# Cpcis_connectors_P4_P5_P6.net
KiCad netlist of a schematic drawn in Altium Designer
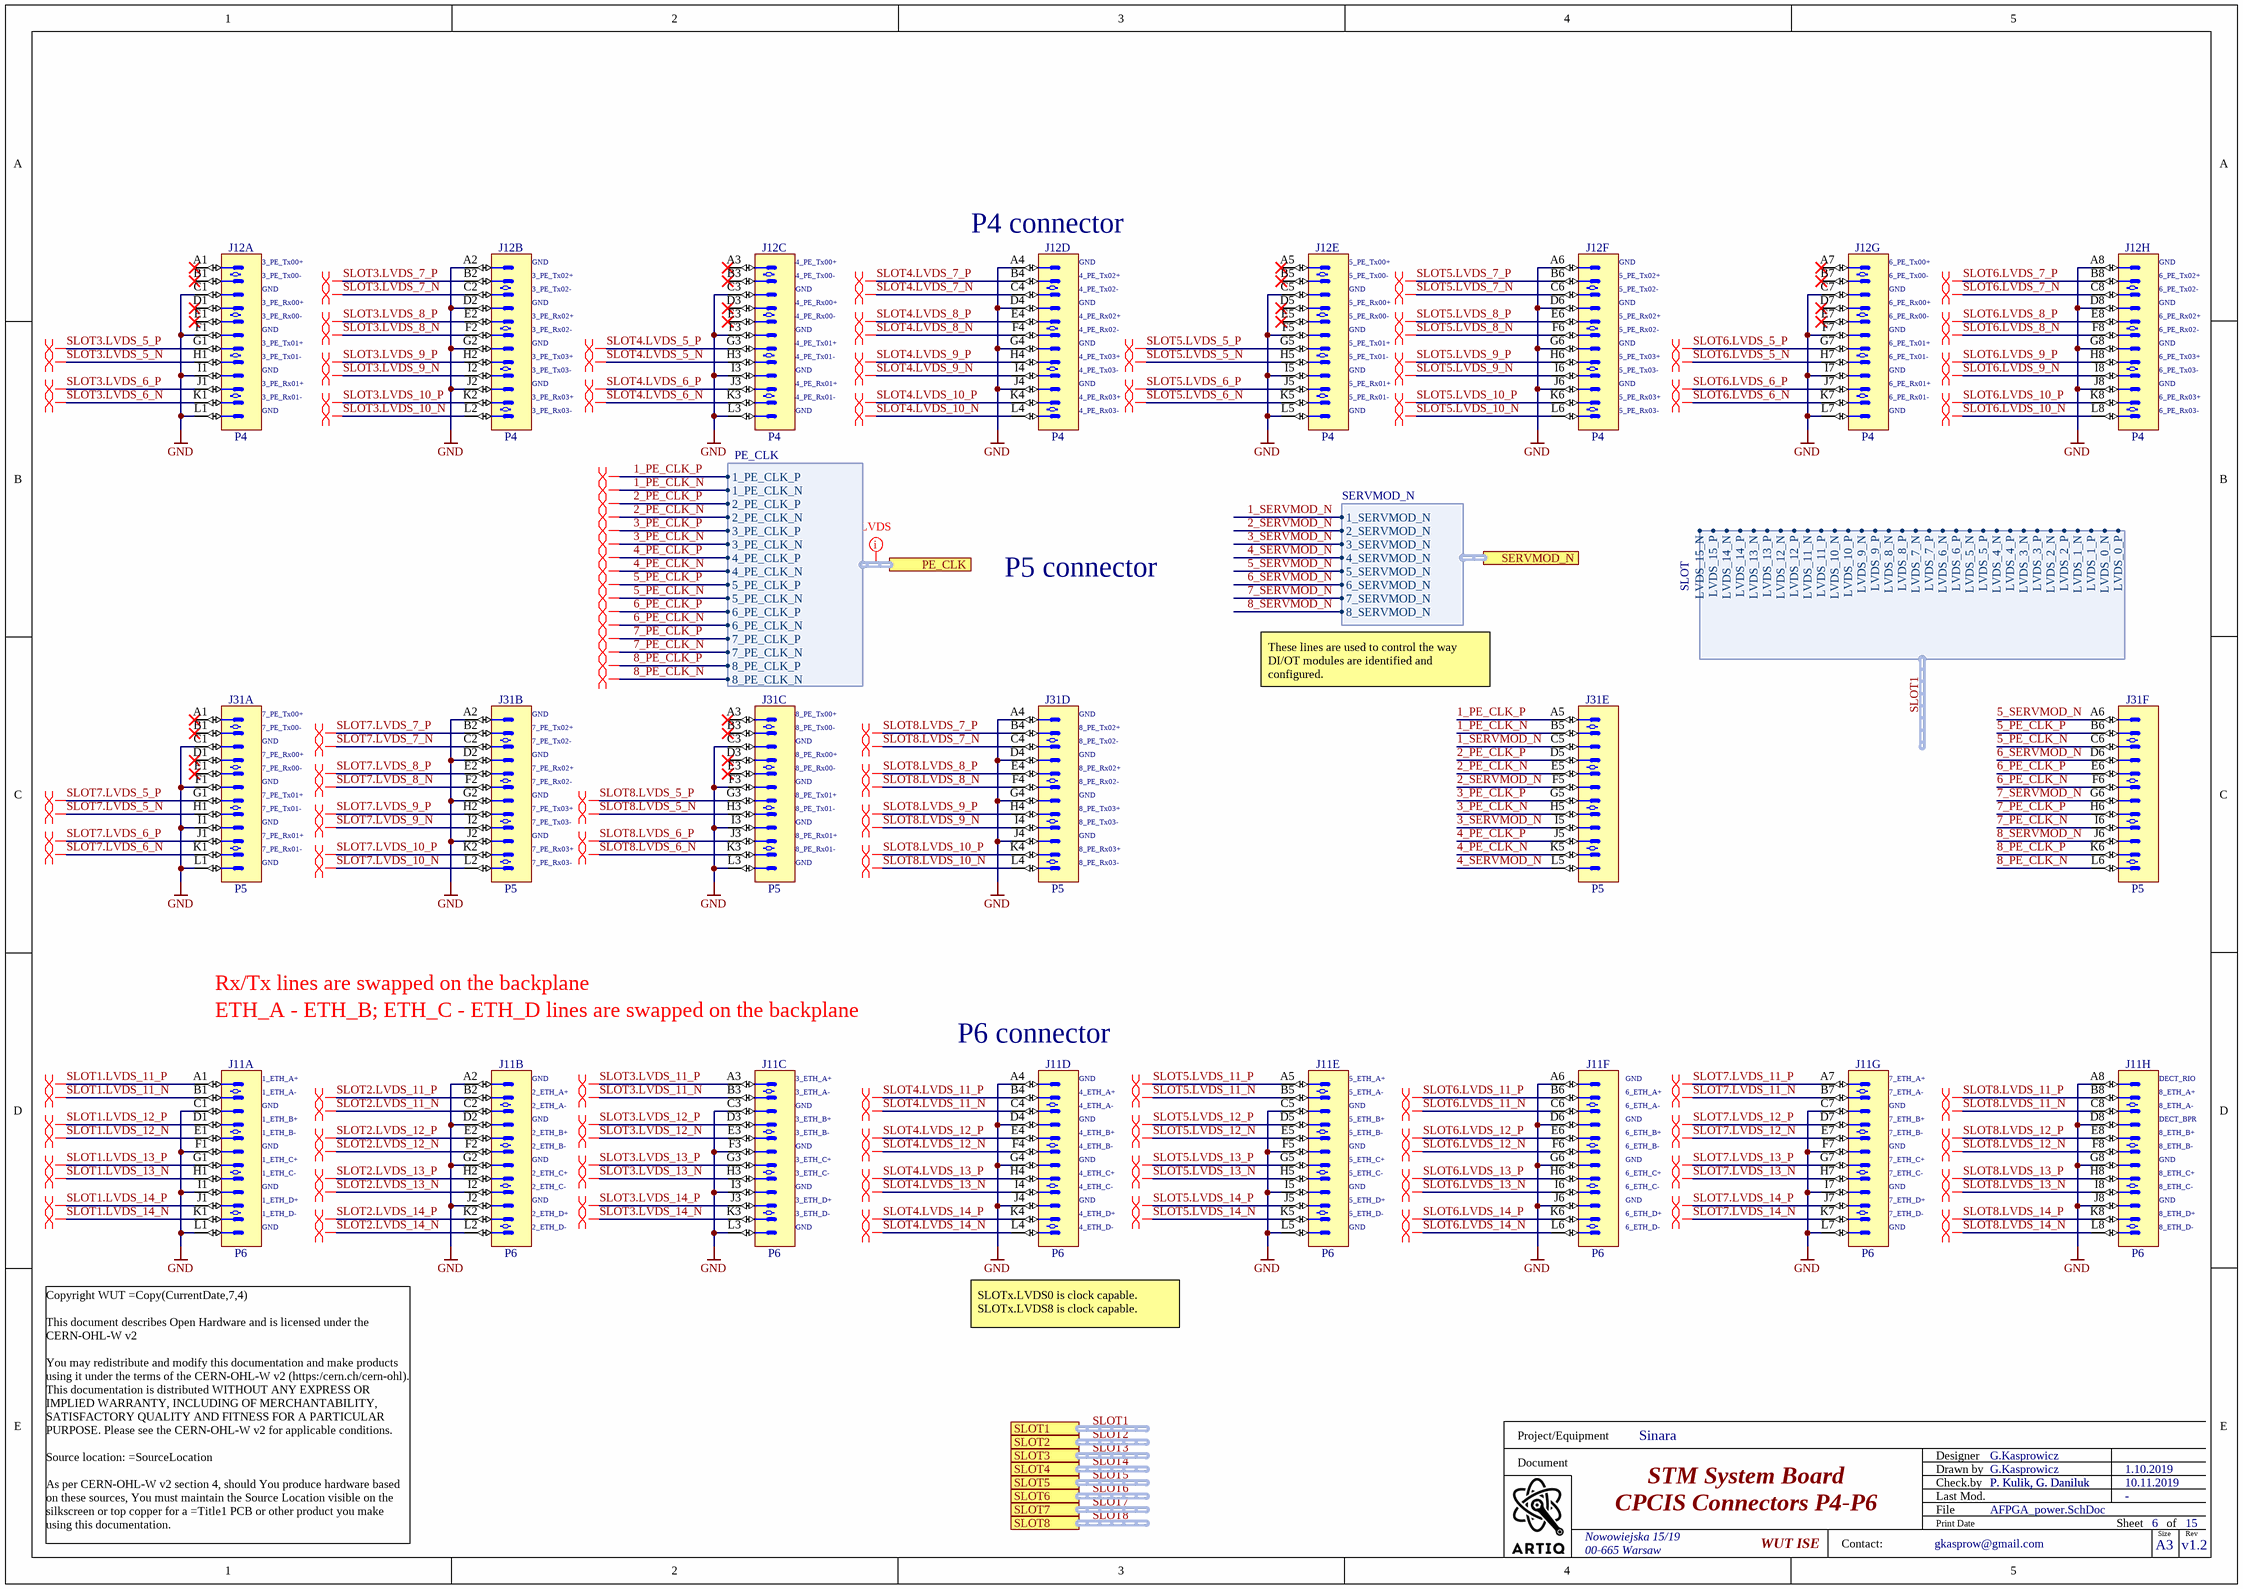
[diagram p0: Cpcis_connectors_P4_P5_P6.SchDoc]

(export (version "E")
  (design (tool "Eeschema 10.0.6"))
  (components
    (comp (ref "J11")
      (value "P6")
      (footprint "AMPHENOL_10052838-101LF")
      (description "96 Contacts Header, 8 Columns, 4 Pairs per Column")
      (fields
        (field (name "PART NUMBER") "AMPHENOL_10052838-101LF")
        (field (name "MANUFACTURER") "AMPHENOL")
        (field (name "AUTHOR") "CERN DEM MR")
      )
      (libsource (lib "Connectors") (part "AMPHENOL_10052838-101LF"))
    )
    (comp (ref "J12")
      (value "P4")
      (footprint "AMPHENOL_10052837-101LF")
      (description "96 Contacts Header, 8 Columns, 4 Pairs per Column")
      (fields
        (field (name "PART NUMBER") "AMPHENOL_10052837-101LF")
        (field (name "MANUFACTURER") "AMPHENOL")
        (field (name "AUTHOR") "CERN DEM MR")
      )
      (libsource (lib "Connectors") (part "AMPHENOL_10052837-101LF"))
    )
    (comp (ref "J31")
      (value "P5")
      (footprint "AMPHENOL_10052824-101LF")
      (description "72 Contacts Header, 6 Columns, 4 Pairs per Column")
      (fields
        (field (name "PART NUMBER") "AMPHENOL_10052824-101LF")
        (field (name "MANUFACTURER") "AMPHENOL")
        (field (name "AUTHOR") "CERN DEM JMW")
      )
      (libsource (lib "Connectors") (part "AMPHENOL_10052824-101LF"))
    )
  )
  (nets
    (net (code "11") (name "/1_PE_CLK_N") (class "Default")
      (node (ref "J31") (pin "B5") (pinfunction "B5_B5") (pintype "bidirectional"))
    )
    (net (code "12") (name "/1_PE_CLK_P") (class "Default")
      (node (ref "J31") (pin "A5") (pinfunction "A5_A5") (pintype "bidirectional"))
    )
    (net (code "13") (name "/1_SERVMOD_N") (class "Default")
      (node (ref "J31") (pin "C5") (pinfunction "C5_C5") (pintype "bidirectional"))
    )
    (net (code "14") (name "/2_PE_CLK_N") (class "Default")
      (node (ref "J31") (pin "E5") (pinfunction "E5_E5") (pintype "bidirectional"))
    )
    (net (code "15") (name "/2_PE_CLK_P") (class "Default")
      (node (ref "J31") (pin "D5") (pinfunction "D5_D5") (pintype "bidirectional"))
    )
    (net (code "16") (name "/2_SERVMOD_N") (class "Default")
      (node (ref "J31") (pin "F5") (pinfunction "F5_F5") (pintype "bidirectional"))
    )
    (net (code "17") (name "/3_PE_CLK_N") (class "Default")
      (node (ref "J31") (pin "H5") (pinfunction "H5_H5") (pintype "bidirectional"))
    )
    (net (code "18") (name "/3_PE_CLK_P") (class "Default")
      (node (ref "J31") (pin "G5") (pinfunction "G5_G5") (pintype "bidirectional"))
    )
    (net (code "19") (name "/3_SERVMOD_N") (class "Default")
      (node (ref "J31") (pin "I5") (pinfunction "I5_I5") (pintype "bidirectional"))
    )
    (net (code "20") (name "/4_PE_CLK_N") (class "Default")
      (node (ref "J31") (pin "K5") (pinfunction "K5_K5") (pintype "bidirectional"))
    )
    (net (code "21") (name "/4_PE_CLK_P") (class "Default")
      (node (ref "J31") (pin "J5") (pinfunction "J5_J5") (pintype "bidirectional"))
    )
    (net (code "22") (name "/4_SERVMOD_N") (class "Default")
      (node (ref "J31") (pin "L5") (pinfunction "L5_L5") (pintype "bidirectional"))
    )
    (net (code "23") (name "/5_PE_CLK_N") (class "Default")
      (node (ref "J31") (pin "C6") (pinfunction "C6_C6") (pintype "bidirectional"))
    )
    (net (code "24") (name "/5_PE_CLK_P") (class "Default")
      (node (ref "J31") (pin "B6") (pinfunction "B6_B6") (pintype "bidirectional"))
    )
    (net (code "25") (name "/5_SERVMOD_N") (class "Default")
      (node (ref "J31") (pin "A6") (pinfunction "A6_A6") (pintype "bidirectional"))
    )
    (net (code "26") (name "/6_PE_CLK_N") (class "Default")
      (node (ref "J31") (pin "F6") (pinfunction "F6_F6") (pintype "bidirectional"))
    )
    (net (code "27") (name "/6_PE_CLK_P") (class "Default")
      (node (ref "J31") (pin "E6") (pinfunction "E6_E6") (pintype "bidirectional"))
    )
    (net (code "28") (name "/6_SERVMOD_N") (class "Default")
      (node (ref "J31") (pin "D6") (pinfunction "D6_D6") (pintype "bidirectional"))
    )
    (net (code "29") (name "/7_PE_CLK_N") (class "Default")
      (node (ref "J31") (pin "I6") (pinfunction "I6_I6") (pintype "bidirectional"))
    )
    (net (code "30") (name "/7_PE_CLK_P") (class "Default")
      (node (ref "J31") (pin "H6") (pinfunction "H6_H6") (pintype "bidirectional"))
    )
    (net (code "31") (name "/7_SERVMOD_N") (class "Default")
      (node (ref "J31") (pin "G6") (pinfunction "G6_G6") (pintype "bidirectional"))
    )
    (net (code "32") (name "/8_PE_CLK_N") (class "Default")
      (node (ref "J31") (pin "L6") (pinfunction "L6_L6") (pintype "bidirectional"))
    )
    (net (code "33") (name "/8_PE_CLK_P") (class "Default")
      (node (ref "J31") (pin "K6") (pinfunction "K6_K6") (pintype "bidirectional"))
    )
    (net (code "34") (name "/8_SERVMOD_N") (class "Default")
      (node (ref "J31") (pin "J6") (pinfunction "J6_J6") (pintype "bidirectional"))
    )
    (net (code "35") (name "/SLOT1.LVDS_11_N") (class "Default")
      (node (ref "J11") (pin "B1") (pinfunction "B1_B1") (pintype "bidirectional"))
    )
    (net (code "36") (name "/SLOT1.LVDS_11_P") (class "Default")
      (node (ref "J11") (pin "A1") (pinfunction "A1_A1") (pintype "bidirectional"))
    )
    (net (code "37") (name "/SLOT1.LVDS_12_N") (class "Default")
      (node (ref "J11") (pin "E1") (pinfunction "E1_E1") (pintype "bidirectional"))
    )
    (net (code "38") (name "/SLOT1.LVDS_12_P") (class "Default")
      (node (ref "J11") (pin "D1") (pinfunction "D1_D1") (pintype "bidirectional"))
    )
    (net (code "39") (name "/SLOT1.LVDS_13_N") (class "Default")
      (node (ref "J11") (pin "H1") (pinfunction "H1_H1") (pintype "bidirectional"))
    )
    (net (code "40") (name "/SLOT1.LVDS_13_P") (class "Default")
      (node (ref "J11") (pin "G1") (pinfunction "G1_G1") (pintype "bidirectional"))
    )
    (net (code "41") (name "/SLOT1.LVDS_14_N") (class "Default")
      (node (ref "J11") (pin "K1") (pinfunction "K1_K1") (pintype "bidirectional"))
    )
    (net (code "42") (name "/SLOT1.LVDS_14_P") (class "Default")
      (node (ref "J11") (pin "J1") (pinfunction "J1_J1") (pintype "bidirectional"))
    )
    (net (code "44") (name "/SLOT2.LVDS_11_N") (class "Default")
      (node (ref "J11") (pin "C2") (pinfunction "C2_C2") (pintype "bidirectional"))
    )
    (net (code "45") (name "/SLOT2.LVDS_11_P") (class "Default")
      (node (ref "J11") (pin "B2") (pinfunction "B2_B2") (pintype "bidirectional"))
    )
    (net (code "46") (name "/SLOT2.LVDS_12_N") (class "Default")
      (node (ref "J11") (pin "F2") (pinfunction "F2_F2") (pintype "bidirectional"))
    )
    (net (code "47") (name "/SLOT2.LVDS_12_P") (class "Default")
      (node (ref "J11") (pin "E2") (pinfunction "E2_E2") (pintype "bidirectional"))
    )
    (net (code "48") (name "/SLOT2.LVDS_13_N") (class "Default")
      (node (ref "J11") (pin "I2") (pinfunction "I2_I2") (pintype "bidirectional"))
    )
    (net (code "49") (name "/SLOT2.LVDS_13_P") (class "Default")
      (node (ref "J11") (pin "H2") (pinfunction "H2_H2") (pintype "bidirectional"))
    )
    (net (code "50") (name "/SLOT2.LVDS_14_N") (class "Default")
      (node (ref "J11") (pin "L2") (pinfunction "L2_L2") (pintype "bidirectional"))
    )
    (net (code "51") (name "/SLOT2.LVDS_14_P") (class "Default")
      (node (ref "J11") (pin "K2") (pinfunction "K2_K2") (pintype "bidirectional"))
    )
    (net (code "52") (name "/SLOT3.LVDS_5_N") (class "Default")
      (node (ref "J12") (pin "H1") (pinfunction "H1_H1") (pintype "bidirectional"))
    )
    (net (code "53") (name "/SLOT3.LVDS_5_P") (class "Default")
      (node (ref "J12") (pin "G1") (pinfunction "G1_G1") (pintype "bidirectional"))
    )
    (net (code "54") (name "/SLOT3.LVDS_6_N") (class "Default")
      (node (ref "J12") (pin "K1") (pinfunction "K1_K1") (pintype "bidirectional"))
    )
    (net (code "55") (name "/SLOT3.LVDS_6_P") (class "Default")
      (node (ref "J12") (pin "J1") (pinfunction "J1_J1") (pintype "bidirectional"))
    )
    (net (code "56") (name "/SLOT3.LVDS_7_N") (class "Default")
      (node (ref "J12") (pin "C2") (pinfunction "C2_C2") (pintype "bidirectional"))
    )
    (net (code "57") (name "/SLOT3.LVDS_7_P") (class "Default")
      (node (ref "J12") (pin "B2") (pinfunction "B2_B2") (pintype "bidirectional"))
    )
    (net (code "58") (name "/SLOT3.LVDS_8_N") (class "Default")
      (node (ref "J12") (pin "F2") (pinfunction "F2_F2") (pintype "bidirectional"))
    )
    (net (code "59") (name "/SLOT3.LVDS_8_P") (class "Default")
      (node (ref "J12") (pin "E2") (pinfunction "E2_E2") (pintype "bidirectional"))
    )
    (net (code "60") (name "/SLOT3.LVDS_9_N") (class "Default")
      (node (ref "J12") (pin "I2") (pinfunction "I2_I2") (pintype "bidirectional"))
    )
    (net (code "61") (name "/SLOT3.LVDS_9_P") (class "Default")
      (node (ref "J12") (pin "H2") (pinfunction "H2_H2") (pintype "bidirectional"))
    )
    (net (code "62") (name "/SLOT3.LVDS_10_N") (class "Default")
      (node (ref "J12") (pin "L2") (pinfunction "L2_L2") (pintype "bidirectional"))
    )
    (net (code "63") (name "/SLOT3.LVDS_10_P") (class "Default")
      (node (ref "J12") (pin "K2") (pinfunction "K2_K2") (pintype "bidirectional"))
    )
    (net (code "64") (name "/SLOT3.LVDS_11_N") (class "Default")
      (node (ref "J11") (pin "B3") (pinfunction "B3_B3") (pintype "bidirectional"))
    )
    (net (code "65") (name "/SLOT3.LVDS_11_P") (class "Default")
      (node (ref "J11") (pin "A3") (pinfunction "A3_A3") (pintype "bidirectional"))
    )
    (net (code "66") (name "/SLOT3.LVDS_12_N") (class "Default")
      (node (ref "J11") (pin "E3") (pinfunction "E3_E3") (pintype "bidirectional"))
    )
    (net (code "67") (name "/SLOT3.LVDS_12_P") (class "Default")
      (node (ref "J11") (pin "D3") (pinfunction "D3_D3") (pintype "bidirectional"))
    )
    (net (code "68") (name "/SLOT3.LVDS_13_N") (class "Default")
      (node (ref "J11") (pin "H3") (pinfunction "H3_H3") (pintype "bidirectional"))
    )
    (net (code "69") (name "/SLOT3.LVDS_13_P") (class "Default")
      (node (ref "J11") (pin "G3") (pinfunction "G3_G3") (pintype "bidirectional"))
    )
    (net (code "70") (name "/SLOT3.LVDS_14_N") (class "Default")
      (node (ref "J11") (pin "K3") (pinfunction "K3_K3") (pintype "bidirectional"))
    )
    (net (code "71") (name "/SLOT3.LVDS_14_P") (class "Default")
      (node (ref "J11") (pin "J3") (pinfunction "J3_J3") (pintype "bidirectional"))
    )
    (net (code "72") (name "/SLOT4.LVDS_5_N") (class "Default")
      (node (ref "J12") (pin "H3") (pinfunction "H3_H3") (pintype "bidirectional"))
    )
    (net (code "73") (name "/SLOT4.LVDS_5_P") (class "Default")
      (node (ref "J12") (pin "G3") (pinfunction "G3_G3") (pintype "bidirectional"))
    )
    (net (code "74") (name "/SLOT4.LVDS_6_N") (class "Default")
      (node (ref "J12") (pin "K3") (pinfunction "K3_K3") (pintype "bidirectional"))
    )
    (net (code "75") (name "/SLOT4.LVDS_6_P") (class "Default")
      (node (ref "J12") (pin "J3") (pinfunction "J3_J3") (pintype "bidirectional"))
    )
    (net (code "76") (name "/SLOT4.LVDS_7_N") (class "Default")
      (node (ref "J12") (pin "C4") (pinfunction "C4_C4") (pintype "bidirectional"))
    )
    (net (code "77") (name "/SLOT4.LVDS_7_P") (class "Default")
      (node (ref "J12") (pin "B4") (pinfunction "B4_B4") (pintype "bidirectional"))
    )
    (net (code "78") (name "/SLOT4.LVDS_8_N") (class "Default")
      (node (ref "J12") (pin "F4") (pinfunction "F4_F4") (pintype "bidirectional"))
    )
    (net (code "79") (name "/SLOT4.LVDS_8_P") (class "Default")
      (node (ref "J12") (pin "E4") (pinfunction "E4_E4") (pintype "bidirectional"))
    )
    (net (code "80") (name "/SLOT4.LVDS_9_N") (class "Default")
      (node (ref "J12") (pin "I4") (pinfunction "I4_I4") (pintype "bidirectional"))
    )
    (net (code "81") (name "/SLOT4.LVDS_9_P") (class "Default")
      (node (ref "J12") (pin "H4") (pinfunction "H4_H4") (pintype "bidirectional"))
    )
    (net (code "82") (name "/SLOT4.LVDS_10_N") (class "Default")
      (node (ref "J12") (pin "L4") (pinfunction "L4_L4") (pintype "bidirectional"))
    )
    (net (code "83") (name "/SLOT4.LVDS_10_P") (class "Default")
      (node (ref "J12") (pin "K4") (pinfunction "K4_K4") (pintype "bidirectional"))
    )
    (net (code "84") (name "/SLOT4.LVDS_11_N") (class "Default")
      (node (ref "J11") (pin "C4") (pinfunction "C4_C4") (pintype "bidirectional"))
    )
    (net (code "85") (name "/SLOT4.LVDS_11_P") (class "Default")
      (node (ref "J11") (pin "B4") (pinfunction "B4_B4") (pintype "bidirectional"))
    )
    (net (code "86") (name "/SLOT4.LVDS_12_N") (class "Default")
      (node (ref "J11") (pin "F4") (pinfunction "F4_F4") (pintype "bidirectional"))
    )
    (net (code "87") (name "/SLOT4.LVDS_12_P") (class "Default")
      (node (ref "J11") (pin "E4") (pinfunction "E4_E4") (pintype "bidirectional"))
    )
    (net (code "88") (name "/SLOT4.LVDS_13_N") (class "Default")
      (node (ref "J11") (pin "I4") (pinfunction "I4_I4") (pintype "bidirectional"))
    )
    (net (code "89") (name "/SLOT4.LVDS_13_P") (class "Default")
      (node (ref "J11") (pin "H4") (pinfunction "H4_H4") (pintype "bidirectional"))
    )
    (net (code "90") (name "/SLOT4.LVDS_14_N") (class "Default")
      (node (ref "J11") (pin "L4") (pinfunction "L4_L4") (pintype "bidirectional"))
    )
    (net (code "91") (name "/SLOT4.LVDS_14_P") (class "Default")
      (node (ref "J11") (pin "K4") (pinfunction "K4_K4") (pintype "bidirectional"))
    )
    (net (code "92") (name "/SLOT5.LVDS_5_N") (class "Default")
      (node (ref "J12") (pin "H5") (pinfunction "H5_H5") (pintype "bidirectional"))
    )
    (net (code "93") (name "/SLOT5.LVDS_5_P") (class "Default")
      (node (ref "J12") (pin "G5") (pinfunction "G5_G5") (pintype "bidirectional"))
    )
    (net (code "94") (name "/SLOT5.LVDS_6_N") (class "Default")
      (node (ref "J12") (pin "K5") (pinfunction "K5_K5") (pintype "bidirectional"))
    )
    (net (code "95") (name "/SLOT5.LVDS_6_P") (class "Default")
      (node (ref "J12") (pin "J5") (pinfunction "J5_J5") (pintype "bidirectional"))
    )
    (net (code "96") (name "/SLOT5.LVDS_7_N") (class "Default")
      (node (ref "J12") (pin "C6") (pinfunction "C6_C6") (pintype "bidirectional"))
    )
    (net (code "97") (name "/SLOT5.LVDS_7_P") (class "Default")
      (node (ref "J12") (pin "B6") (pinfunction "B6_B6") (pintype "bidirectional"))
    )
    (net (code "98") (name "/SLOT5.LVDS_8_N") (class "Default")
      (node (ref "J12") (pin "F6") (pinfunction "F6_F6") (pintype "bidirectional"))
    )
    (net (code "99") (name "/SLOT5.LVDS_8_P") (class "Default")
      (node (ref "J12") (pin "E6") (pinfunction "E6_E6") (pintype "bidirectional"))
    )
    (net (code "100") (name "/SLOT5.LVDS_9_N") (class "Default")
      (node (ref "J12") (pin "I6") (pinfunction "I6_I6") (pintype "bidirectional"))
    )
    (net (code "101") (name "/SLOT5.LVDS_9_P") (class "Default")
      (node (ref "J12") (pin "H6") (pinfunction "H6_H6") (pintype "bidirectional"))
    )
    (net (code "102") (name "/SLOT5.LVDS_10_N") (class "Default")
      (node (ref "J12") (pin "L6") (pinfunction "L6_L6") (pintype "bidirectional"))
    )
    (net (code "103") (name "/SLOT5.LVDS_10_P") (class "Default")
      (node (ref "J12") (pin "K6") (pinfunction "K6_K6") (pintype "bidirectional"))
    )
    (net (code "104") (name "/SLOT5.LVDS_11_N") (class "Default")
      (node (ref "J11") (pin "B5") (pinfunction "B5_B5") (pintype "bidirectional"))
    )
    (net (code "105") (name "/SLOT5.LVDS_11_P") (class "Default")
      (node (ref "J11") (pin "A5") (pinfunction "A5_A5") (pintype "bidirectional"))
    )
    (net (code "106") (name "/SLOT5.LVDS_12_N") (class "Default")
      (node (ref "J11") (pin "E5") (pinfunction "E5_E5") (pintype "bidirectional"))
    )
    (net (code "107") (name "/SLOT5.LVDS_12_P") (class "Default")
      (node (ref "J11") (pin "D5") (pinfunction "D5_D5") (pintype "bidirectional"))
    )
    (net (code "108") (name "/SLOT5.LVDS_13_N") (class "Default")
      (node (ref "J11") (pin "H5") (pinfunction "H5_H5") (pintype "bidirectional"))
    )
    (net (code "109") (name "/SLOT5.LVDS_13_P") (class "Default")
      (node (ref "J11") (pin "G5") (pinfunction "G5_G5") (pintype "bidirectional"))
    )
    (net (code "110") (name "/SLOT5.LVDS_14_N") (class "Default")
      (node (ref "J11") (pin "K5") (pinfunction "K5_K5") (pintype "bidirectional"))
    )
    (net (code "111") (name "/SLOT5.LVDS_14_P") (class "Default")
      (node (ref "J11") (pin "J5") (pinfunction "J5_J5") (pintype "bidirectional"))
    )
    (net (code "112") (name "/SLOT6.LVDS_5_N") (class "Default")
      (node (ref "J12") (pin "H7") (pinfunction "H7_H7") (pintype "bidirectional"))
    )
    (net (code "113") (name "/SLOT6.LVDS_5_P") (class "Default")
      (node (ref "J12") (pin "G7") (pinfunction "G7_G7") (pintype "bidirectional"))
    )
    (net (code "114") (name "/SLOT6.LVDS_6_N") (class "Default")
      (node (ref "J12") (pin "K7") (pinfunction "K7_K7") (pintype "bidirectional"))
    )
    (net (code "115") (name "/SLOT6.LVDS_6_P") (class "Default")
      (node (ref "J12") (pin "J7") (pinfunction "J7_J7") (pintype "bidirectional"))
    )
    (net (code "116") (name "/SLOT6.LVDS_7_N") (class "Default")
      (node (ref "J12") (pin "C8") (pinfunction "C8_C8") (pintype "bidirectional"))
    )
    (net (code "117") (name "/SLOT6.LVDS_7_P") (class "Default")
      (node (ref "J12") (pin "B8") (pinfunction "B8_B8") (pintype "bidirectional"))
    )
    (net (code "118") (name "/SLOT6.LVDS_8_N") (class "Default")
      (node (ref "J12") (pin "F8") (pinfunction "F8_F8") (pintype "bidirectional"))
    )
    (net (code "119") (name "/SLOT6.LVDS_8_P") (class "Default")
      (node (ref "J12") (pin "E8") (pinfunction "E8_E8") (pintype "bidirectional"))
    )
    (net (code "120") (name "/SLOT6.LVDS_9_N") (class "Default")
      (node (ref "J12") (pin "I8") (pinfunction "I8_I8") (pintype "bidirectional"))
    )
    (net (code "121") (name "/SLOT6.LVDS_9_P") (class "Default")
      (node (ref "J12") (pin "H8") (pinfunction "H8_H8") (pintype "bidirectional"))
    )
    (net (code "122") (name "/SLOT6.LVDS_10_N") (class "Default")
      (node (ref "J12") (pin "L8") (pinfunction "L8_L8") (pintype "bidirectional"))
    )
    (net (code "123") (name "/SLOT6.LVDS_10_P") (class "Default")
      (node (ref "J12") (pin "K8") (pinfunction "K8_K8") (pintype "bidirectional"))
    )
    (net (code "124") (name "/SLOT6.LVDS_11_N") (class "Default")
      (node (ref "J11") (pin "C6") (pinfunction "C6_C6") (pintype "bidirectional"))
    )
    (net (code "125") (name "/SLOT6.LVDS_11_P") (class "Default")
      (node (ref "J11") (pin "B6") (pinfunction "B6_B6") (pintype "bidirectional"))
    )
    (net (code "126") (name "/SLOT6.LVDS_12_N") (class "Default")
      (node (ref "J11") (pin "F6") (pinfunction "F6_F6") (pintype "bidirectional"))
    )
    (net (code "127") (name "/SLOT6.LVDS_12_P") (class "Default")
      (node (ref "J11") (pin "E6") (pinfunction "E6_E6") (pintype "bidirectional"))
    )
    (net (code "128") (name "/SLOT6.LVDS_13_N") (class "Default")
      (node (ref "J11") (pin "I6") (pinfunction "I6_I6") (pintype "bidirectional"))
    )
    (net (code "129") (name "/SLOT6.LVDS_13_P") (class "Default")
      (node (ref "J11") (pin "H6") (pinfunction "H6_H6") (pintype "bidirectional"))
    )
    (net (code "130") (name "/SLOT6.LVDS_14_N") (class "Default")
      (node (ref "J11") (pin "L6") (pinfunction "L6_L6") (pintype "bidirectional"))
    )
    (net (code "131") (name "/SLOT6.LVDS_14_P") (class "Default")
      (node (ref "J11") (pin "K6") (pinfunction "K6_K6") (pintype "bidirectional"))
    )
    (net (code "132") (name "/SLOT7.LVDS_5_N") (class "Default")
      (node (ref "J31") (pin "H1") (pinfunction "H1_H1") (pintype "bidirectional"))
    )
    (net (code "133") (name "/SLOT7.LVDS_5_P") (class "Default")
      (node (ref "J31") (pin "G1") (pinfunction "G1_G1") (pintype "bidirectional"))
    )
    (net (code "134") (name "/SLOT7.LVDS_6_N") (class "Default")
      (node (ref "J31") (pin "K1") (pinfunction "K1_K1") (pintype "bidirectional"))
    )
    (net (code "135") (name "/SLOT7.LVDS_6_P") (class "Default")
      (node (ref "J31") (pin "J1") (pinfunction "J1_J1") (pintype "bidirectional"))
    )
    (net (code "136") (name "/SLOT7.LVDS_7_N") (class "Default")
      (node (ref "J31") (pin "C2") (pinfunction "C2_C2") (pintype "bidirectional"))
    )
    (net (code "137") (name "/SLOT7.LVDS_7_P") (class "Default")
      (node (ref "J31") (pin "B2") (pinfunction "B2_B2") (pintype "bidirectional"))
    )
    (net (code "138") (name "/SLOT7.LVDS_8_N") (class "Default")
      (node (ref "J31") (pin "F2") (pinfunction "F2_F2") (pintype "bidirectional"))
    )
    (net (code "139") (name "/SLOT7.LVDS_8_P") (class "Default")
      (node (ref "J31") (pin "E2") (pinfunction "E2_E2") (pintype "bidirectional"))
    )
    (net (code "140") (name "/SLOT7.LVDS_9_N") (class "Default")
      (node (ref "J31") (pin "I2") (pinfunction "I2_I2") (pintype "bidirectional"))
    )
    (net (code "141") (name "/SLOT7.LVDS_9_P") (class "Default")
      (node (ref "J31") (pin "H2") (pinfunction "H2_H2") (pintype "bidirectional"))
    )
    (net (code "142") (name "/SLOT7.LVDS_10_N") (class "Default")
      (node (ref "J31") (pin "L2") (pinfunction "L2_L2") (pintype "bidirectional"))
    )
    (net (code "143") (name "/SLOT7.LVDS_10_P") (class "Default")
      (node (ref "J31") (pin "K2") (pinfunction "K2_K2") (pintype "bidirectional"))
    )
    (net (code "144") (name "/SLOT7.LVDS_11_N") (class "Default")
      (node (ref "J11") (pin "B7") (pinfunction "B7_B7") (pintype "bidirectional"))
    )
    (net (code "145") (name "/SLOT7.LVDS_11_P") (class "Default")
      (node (ref "J11") (pin "A7") (pinfunction "A7_A7") (pintype "bidirectional"))
    )
    (net (code "146") (name "/SLOT7.LVDS_12_N") (class "Default")
      (node (ref "J11") (pin "E7") (pinfunction "E7_E7") (pintype "bidirectional"))
    )
    (net (code "147") (name "/SLOT7.LVDS_12_P") (class "Default")
      (node (ref "J11") (pin "D7") (pinfunction "D7_D7") (pintype "bidirectional"))
    )
    (net (code "148") (name "/SLOT7.LVDS_13_N") (class "Default")
      (node (ref "J11") (pin "H7") (pinfunction "H7_H7") (pintype "bidirectional"))
    )
    (net (code "149") (name "/SLOT7.LVDS_13_P") (class "Default")
      (node (ref "J11") (pin "G7") (pinfunction "G7_G7") (pintype "bidirectional"))
    )
    (net (code "150") (name "/SLOT7.LVDS_14_N") (class "Default")
      (node (ref "J11") (pin "K7") (pinfunction "K7_K7") (pintype "bidirectional"))
    )
    (net (code "151") (name "/SLOT7.LVDS_14_P") (class "Default")
      (node (ref "J11") (pin "J7") (pinfunction "J7_J7") (pintype "bidirectional"))
    )
    (net (code "152") (name "/SLOT8.LVDS_5_N") (class "Default")
      (node (ref "J31") (pin "H3") (pinfunction "H3_H3") (pintype "bidirectional"))
    )
    (net (code "153") (name "/SLOT8.LVDS_5_P") (class "Default")
      (node (ref "J31") (pin "G3") (pinfunction "G3_G3") (pintype "bidirectional"))
    )
    (net (code "154") (name "/SLOT8.LVDS_6_N") (class "Default")
      (node (ref "J31") (pin "K3") (pinfunction "K3_K3") (pintype "bidirectional"))
    )
    (net (code "155") (name "/SLOT8.LVDS_6_P") (class "Default")
      (node (ref "J31") (pin "J3") (pinfunction "J3_J3") (pintype "bidirectional"))
    )
    (net (code "156") (name "/SLOT8.LVDS_7_N") (class "Default")
      (node (ref "J31") (pin "C4") (pinfunction "C4_C4") (pintype "bidirectional"))
    )
    (net (code "157") (name "/SLOT8.LVDS_7_P") (class "Default")
      (node (ref "J31") (pin "B4") (pinfunction "B4_B4") (pintype "bidirectional"))
    )
    (net (code "158") (name "/SLOT8.LVDS_8_N") (class "Default")
      (node (ref "J31") (pin "F4") (pinfunction "F4_F4") (pintype "bidirectional"))
    )
    (net (code "159") (name "/SLOT8.LVDS_8_P") (class "Default")
      (node (ref "J31") (pin "E4") (pinfunction "E4_E4") (pintype "bidirectional"))
    )
    (net (code "160") (name "/SLOT8.LVDS_9_N") (class "Default")
      (node (ref "J31") (pin "I4") (pinfunction "I4_I4") (pintype "bidirectional"))
    )
    (net (code "161") (name "/SLOT8.LVDS_9_P") (class "Default")
      (node (ref "J31") (pin "H4") (pinfunction "H4_H4") (pintype "bidirectional"))
    )
    (net (code "162") (name "/SLOT8.LVDS_10_N") (class "Default")
      (node (ref "J31") (pin "L4") (pinfunction "L4_L4") (pintype "bidirectional"))
    )
    (net (code "163") (name "/SLOT8.LVDS_10_P") (class "Default")
      (node (ref "J31") (pin "K4") (pinfunction "K4_K4") (pintype "bidirectional"))
    )
    (net (code "164") (name "/SLOT8.LVDS_11_N") (class "Default")
      (node (ref "J11") (pin "C8") (pinfunction "C8_C8") (pintype "bidirectional"))
    )
    (net (code "165") (name "/SLOT8.LVDS_11_P") (class "Default")
      (node (ref "J11") (pin "B8") (pinfunction "B8_B8") (pintype "bidirectional"))
    )
    (net (code "166") (name "/SLOT8.LVDS_12_N") (class "Default")
      (node (ref "J11") (pin "F8") (pinfunction "F8_F8") (pintype "bidirectional"))
    )
    (net (code "167") (name "/SLOT8.LVDS_12_P") (class "Default")
      (node (ref "J11") (pin "E8") (pinfunction "E8_E8") (pintype "bidirectional"))
    )
    (net (code "168") (name "/SLOT8.LVDS_13_N") (class "Default")
      (node (ref "J11") (pin "I8") (pinfunction "I8_I8") (pintype "bidirectional"))
    )
    (net (code "169") (name "/SLOT8.LVDS_13_P") (class "Default")
      (node (ref "J11") (pin "H8") (pinfunction "H8_H8") (pintype "bidirectional"))
    )
    (net (code "170") (name "/SLOT8.LVDS_14_N") (class "Default")
      (node (ref "J11") (pin "L8") (pinfunction "L8_L8") (pintype "bidirectional"))
    )
    (net (code "171") (name "/SLOT8.LVDS_14_P") (class "Default")
      (node (ref "J11") (pin "K8") (pinfunction "K8_K8") (pintype "bidirectional"))
    )
    (net (code "181") (name "GND") (class "Default")
      (node (ref "J11") (pin "A2") (pinfunction "A2_A2") (pintype "bidirectional"))
      (node (ref "J11") (pin "A4") (pinfunction "A4_A4") (pintype "bidirectional"))
      (node (ref "J11") (pin "A6") (pinfunction "A6_A6") (pintype "bidirectional"))
      (node (ref "J11") (pin "A8") (pinfunction "A8_A8") (pintype "bidirectional"))
      (node (ref "J11") (pin "C1") (pinfunction "C1_C1") (pintype "bidirectional"))
      (node (ref "J11") (pin "C3") (pinfunction "C3_C3") (pintype "bidirectional"))
      (node (ref "J11") (pin "C5") (pinfunction "C5_C5") (pintype "bidirectional"))
      (node (ref "J11") (pin "C7") (pinfunction "C7_C7") (pintype "bidirectional"))
      (node (ref "J11") (pin "D2") (pinfunction "D2_D2") (pintype "bidirectional"))
      (node (ref "J11") (pin "D4") (pinfunction "D4_D4") (pintype "bidirectional"))
      (node (ref "J11") (pin "D6") (pinfunction "D6_D6") (pintype "bidirectional"))
      (node (ref "J11") (pin "D8") (pinfunction "D8_D8") (pintype "bidirectional"))
      (node (ref "J11") (pin "F1") (pinfunction "F1_F1") (pintype "bidirectional"))
      (node (ref "J11") (pin "F3") (pinfunction "F3_F3") (pintype "bidirectional"))
      (node (ref "J11") (pin "F5") (pinfunction "F5_F5") (pintype "bidirectional"))
      (node (ref "J11") (pin "F7") (pinfunction "F7_F7") (pintype "bidirectional"))
      (node (ref "J11") (pin "G2") (pinfunction "G2_G2") (pintype "bidirectional"))
      (node (ref "J11") (pin "G4") (pinfunction "G4_G4") (pintype "bidirectional"))
      (node (ref "J11") (pin "G6") (pinfunction "G6_G6") (pintype "bidirectional"))
      (node (ref "J11") (pin "G8") (pinfunction "G8_G8") (pintype "bidirectional"))
      (node (ref "J11") (pin "I1") (pinfunction "I1_I1") (pintype "bidirectional"))
      (node (ref "J11") (pin "I3") (pinfunction "I3_I3") (pintype "bidirectional"))
      (node (ref "J11") (pin "I5") (pinfunction "I5_I5") (pintype "bidirectional"))
      (node (ref "J11") (pin "I7") (pinfunction "I7_I7") (pintype "bidirectional"))
      (node (ref "J11") (pin "J2") (pinfunction "J2_J2") (pintype "bidirectional"))
      (node (ref "J11") (pin "J4") (pinfunction "J4_J4") (pintype "bidirectional"))
      (node (ref "J11") (pin "J6") (pinfunction "J6_J6") (pintype "bidirectional"))
      (node (ref "J11") (pin "J8") (pinfunction "J8_J8") (pintype "bidirectional"))
      (node (ref "J11") (pin "L1") (pinfunction "L1_L1") (pintype "bidirectional"))
      (node (ref "J11") (pin "L3") (pinfunction "L3_L3") (pintype "bidirectional"))
      (node (ref "J11") (pin "L5") (pinfunction "L5_L5") (pintype "bidirectional"))
      (node (ref "J11") (pin "L7") (pinfunction "L7_L7") (pintype "bidirectional"))
      (node (ref "J12") (pin "A2") (pinfunction "A2_A2") (pintype "bidirectional"))
      (node (ref "J12") (pin "A4") (pinfunction "A4_A4") (pintype "bidirectional"))
      (node (ref "J12") (pin "A6") (pinfunction "A6_A6") (pintype "bidirectional"))
      (node (ref "J12") (pin "A8") (pinfunction "A8_A8") (pintype "bidirectional"))
      (node (ref "J12") (pin "C1") (pinfunction "C1_C1") (pintype "bidirectional"))
      (node (ref "J12") (pin "C3") (pinfunction "C3_C3") (pintype "bidirectional"))
      (node (ref "J12") (pin "C5") (pinfunction "C5_C5") (pintype "bidirectional"))
      (node (ref "J12") (pin "C7") (pinfunction "C7_C7") (pintype "bidirectional"))
      (node (ref "J12") (pin "D2") (pinfunction "D2_D2") (pintype "bidirectional"))
      (node (ref "J12") (pin "D4") (pinfunction "D4_D4") (pintype "bidirectional"))
      (node (ref "J12") (pin "D6") (pinfunction "D6_D6") (pintype "bidirectional"))
      (node (ref "J12") (pin "D8") (pinfunction "D8_D8") (pintype "bidirectional"))
      (node (ref "J12") (pin "F1") (pinfunction "F1_F1") (pintype "bidirectional"))
      (node (ref "J12") (pin "F3") (pinfunction "F3_F3") (pintype "bidirectional"))
      (node (ref "J12") (pin "F5") (pinfunction "F5_F5") (pintype "bidirectional"))
      (node (ref "J12") (pin "F7") (pinfunction "F7_F7") (pintype "bidirectional"))
      (node (ref "J12") (pin "G2") (pinfunction "G2_G2") (pintype "bidirectional"))
      (node (ref "J12") (pin "G4") (pinfunction "G4_G4") (pintype "bidirectional"))
      (node (ref "J12") (pin "G6") (pinfunction "G6_G6") (pintype "bidirectional"))
      (node (ref "J12") (pin "G8") (pinfunction "G8_G8") (pintype "bidirectional"))
      (node (ref "J12") (pin "I1") (pinfunction "I1_I1") (pintype "bidirectional"))
      (node (ref "J12") (pin "I3") (pinfunction "I3_I3") (pintype "bidirectional"))
      (node (ref "J12") (pin "I5") (pinfunction "I5_I5") (pintype "bidirectional"))
      (node (ref "J12") (pin "I7") (pinfunction "I7_I7") (pintype "bidirectional"))
      (node (ref "J12") (pin "J2") (pinfunction "J2_J2") (pintype "bidirectional"))
      (node (ref "J12") (pin "J4") (pinfunction "J4_J4") (pintype "bidirectional"))
      (node (ref "J12") (pin "J6") (pinfunction "J6_J6") (pintype "bidirectional"))
      (node (ref "J12") (pin "J8") (pinfunction "J8_J8") (pintype "bidirectional"))
      (node (ref "J12") (pin "L1") (pinfunction "L1_L1") (pintype "bidirectional"))
      (node (ref "J12") (pin "L3") (pinfunction "L3_L3") (pintype "bidirectional"))
      (node (ref "J12") (pin "L5") (pinfunction "L5_L5") (pintype "bidirectional"))
      (node (ref "J12") (pin "L7") (pinfunction "L7_L7") (pintype "bidirectional"))
      (node (ref "J31") (pin "A2") (pinfunction "A2_A2") (pintype "bidirectional"))
      (node (ref "J31") (pin "A4") (pinfunction "A4_A4") (pintype "bidirectional"))
      (node (ref "J31") (pin "C1") (pinfunction "C1_C1") (pintype "bidirectional"))
      (node (ref "J31") (pin "C3") (pinfunction "C3_C3") (pintype "bidirectional"))
      (node (ref "J31") (pin "D2") (pinfunction "D2_D2") (pintype "bidirectional"))
      (node (ref "J31") (pin "D4") (pinfunction "D4_D4") (pintype "bidirectional"))
      (node (ref "J31") (pin "F1") (pinfunction "F1_F1") (pintype "bidirectional"))
      (node (ref "J31") (pin "F3") (pinfunction "F3_F3") (pintype "bidirectional"))
      (node (ref "J31") (pin "G2") (pinfunction "G2_G2") (pintype "bidirectional"))
      (node (ref "J31") (pin "G4") (pinfunction "G4_G4") (pintype "bidirectional"))
      (node (ref "J31") (pin "I1") (pinfunction "I1_I1") (pintype "bidirectional"))
      (node (ref "J31") (pin "I3") (pinfunction "I3_I3") (pintype "bidirectional"))
      (node (ref "J31") (pin "J2") (pinfunction "J2_J2") (pintype "bidirectional"))
      (node (ref "J31") (pin "J4") (pinfunction "J4_J4") (pintype "bidirectional"))
      (node (ref "J31") (pin "L1") (pinfunction "L1_L1") (pintype "bidirectional"))
      (node (ref "J31") (pin "L3") (pinfunction "L3_L3") (pintype "bidirectional"))
    )
    (net (code "182") (name "unconnected-(J12-PadA1)") (class "Default")
      (node (ref "J12") (pin "A1") (pinfunction "A1_A1") (pintype "bidirectional+no_connect"))
    )
    (net (code "183") (name "unconnected-(J12-PadA3)") (class "Default")
      (node (ref "J12") (pin "A3") (pinfunction "A3_A3") (pintype "bidirectional+no_connect"))
    )
    (net (code "184") (name "unconnected-(J12-PadA5)") (class "Default")
      (node (ref "J12") (pin "A5") (pinfunction "A5_A5") (pintype "bidirectional+no_connect"))
    )
    (net (code "185") (name "unconnected-(J12-PadA7)") (class "Default")
      (node (ref "J12") (pin "A7") (pinfunction "A7_A7") (pintype "bidirectional+no_connect"))
    )
    (net (code "186") (name "unconnected-(J12-PadB1)") (class "Default")
      (node (ref "J12") (pin "B1") (pinfunction "B1_B1") (pintype "bidirectional+no_connect"))
    )
    (net (code "187") (name "unconnected-(J12-PadB3)") (class "Default")
      (node (ref "J12") (pin "B3") (pinfunction "B3_B3") (pintype "bidirectional+no_connect"))
    )
    (net (code "188") (name "unconnected-(J12-PadB5)") (class "Default")
      (node (ref "J12") (pin "B5") (pinfunction "B5_B5") (pintype "bidirectional+no_connect"))
    )
    (net (code "189") (name "unconnected-(J12-PadB7)") (class "Default")
      (node (ref "J12") (pin "B7") (pinfunction "B7_B7") (pintype "bidirectional+no_connect"))
    )
    (net (code "190") (name "unconnected-(J12-PadD1)") (class "Default")
      (node (ref "J12") (pin "D1") (pinfunction "D1_D1") (pintype "bidirectional+no_connect"))
    )
    (net (code "191") (name "unconnected-(J12-PadD3)") (class "Default")
      (node (ref "J12") (pin "D3") (pinfunction "D3_D3") (pintype "bidirectional+no_connect"))
    )
    (net (code "192") (name "unconnected-(J12-PadD5)") (class "Default")
      (node (ref "J12") (pin "D5") (pinfunction "D5_D5") (pintype "bidirectional+no_connect"))
    )
    (net (code "193") (name "unconnected-(J12-PadD7)") (class "Default")
      (node (ref "J12") (pin "D7") (pinfunction "D7_D7") (pintype "bidirectional+no_connect"))
    )
    (net (code "194") (name "unconnected-(J12-PadE1)") (class "Default")
      (node (ref "J12") (pin "E1") (pinfunction "E1_E1") (pintype "bidirectional+no_connect"))
    )
    (net (code "195") (name "unconnected-(J12-PadE3)") (class "Default")
      (node (ref "J12") (pin "E3") (pinfunction "E3_E3") (pintype "bidirectional+no_connect"))
    )
    (net (code "196") (name "unconnected-(J12-PadE5)") (class "Default")
      (node (ref "J12") (pin "E5") (pinfunction "E5_E5") (pintype "bidirectional+no_connect"))
    )
    (net (code "197") (name "unconnected-(J12-PadE7)") (class "Default")
      (node (ref "J12") (pin "E7") (pinfunction "E7_E7") (pintype "bidirectional+no_connect"))
    )
    (net (code "198") (name "unconnected-(J31-PadA1)") (class "Default")
      (node (ref "J31") (pin "A1") (pinfunction "A1_A1") (pintype "bidirectional+no_connect"))
    )
    (net (code "199") (name "unconnected-(J31-PadA3)") (class "Default")
      (node (ref "J31") (pin "A3") (pinfunction "A3_A3") (pintype "bidirectional+no_connect"))
    )
    (net (code "200") (name "unconnected-(J31-PadB1)") (class "Default")
      (node (ref "J31") (pin "B1") (pinfunction "B1_B1") (pintype "bidirectional+no_connect"))
    )
    (net (code "201") (name "unconnected-(J31-PadB3)") (class "Default")
      (node (ref "J31") (pin "B3") (pinfunction "B3_B3") (pintype "bidirectional+no_connect"))
    )
    (net (code "202") (name "unconnected-(J31-PadD1)") (class "Default")
      (node (ref "J31") (pin "D1") (pinfunction "D1_D1") (pintype "bidirectional+no_connect"))
    )
    (net (code "203") (name "unconnected-(J31-PadD3)") (class "Default")
      (node (ref "J31") (pin "D3") (pinfunction "D3_D3") (pintype "bidirectional+no_connect"))
    )
    (net (code "204") (name "unconnected-(J31-PadE1)") (class "Default")
      (node (ref "J31") (pin "E1") (pinfunction "E1_E1") (pintype "bidirectional+no_connect"))
    )
    (net (code "205") (name "unconnected-(J31-PadE3)") (class "Default")
      (node (ref "J31") (pin "E3") (pinfunction "E3_E3") (pintype "bidirectional+no_connect"))
    )
  )
)
